# SD_USB_FMU_REV_2A.net
KiCad netlist of a schematic drawn in Altium Designer
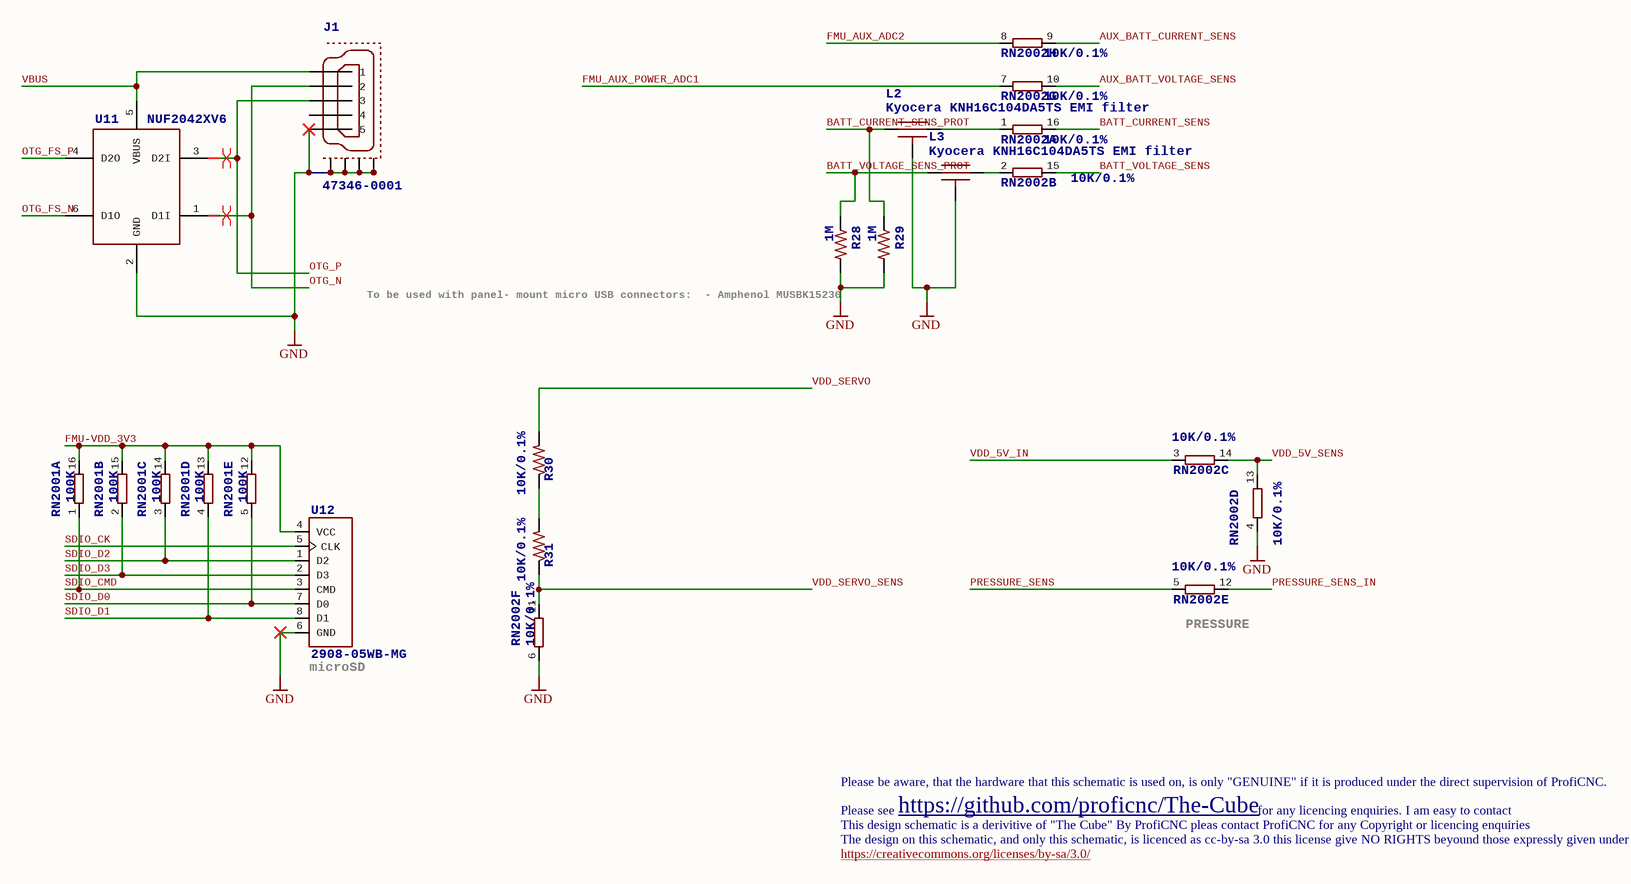
[diagram p0: SD_USB_FMU_REV_2A.SchDoc]

(export (version "E")
  (design (tool "Eeschema 10.0.6"))
  (components
    (comp (ref "J1")
      (value "47346-0001")
      (footprint "MOLEX-47346-0001")
      (description "MICRO USB B, BOTTOM MOUNT")
      (libsource (lib "pixhawk2") (part "MOLEX-47346-0001"))
    )
    (comp (ref "L2")
      (value "Kyocera KNH16C104DA5TS EMI filter")
      (footprint "KYOCERA-KNH16-DA")
      (description "FILTER CAP 0.1UF 2A 25V 0603")
      (libsource (lib "pixhawk2") (part "KNH16C104DA5TS"))
    )
    (comp (ref "L3")
      (value "Kyocera KNH16C104DA5TS EMI filter")
      (footprint "KYOCERA-KNH16-DA")
      (description "FILTER CAP 0.1UF 2A 25V 0603")
      (libsource (lib "pixhawk2") (part "KNH16C104DA5TS"))
    )
    (comp (ref "R28")
      (value "1M")
      (footprint "0402-RES")
      (description "RES 1M OHM 1/16W 1% 0402 SMD")
      (libsource (lib "pixhawk2") (part "RESISTOR0402-RES"))
    )
    (comp (ref "R29")
      (value "1M")
      (footprint "0402-RES")
      (description "RES 1M OHM 1/16W 1% 0402 SMD")
      (libsource (lib "pixhawk2") (part "RESISTOR0402-RES"))
    )
    (comp (ref "R30")
      (value "10K/0.1%")
      (footprint "0402-RES")
      (description "RES 10K OHM 1/16W .1% 0402 SMD")
      (libsource (lib "pixhawk2") (part "RESISTOR0402-RES"))
    )
    (comp (ref "R31")
      (value "10K/0.1%")
      (footprint "0402-RES")
      (description "RES 10K OHM 1/16W .1% 0402 SMD")
      (libsource (lib "pixhawk2") (part "RESISTOR0402-RES"))
    )
    (comp (ref "RN2001")
      (value "100K")
      (footprint "EXB2HV")
      (description "RES ARRAY 100K OHM 8 RES 1506")
      (libsource (lib "pixhawk2") (part "8R-NEXB2HV-100K"))
    )
    (comp (ref "RN2002")
      (value "10K/0.1%")
      (footprint "EXB2HV")
      (description "RES ARRAY 10K OHM 8 RES 1506")
      (libsource (lib "pixhawk2") (part "8R-NEXB2HV-10K"))
    )
    (comp (ref "U11")
      (value "NUF2042XV6")
      (footprint "SOT563-6")
      (description "IC FILTER USB ESD PROTECT SOT363")
      (libsource (lib "pixhawk2") (part "NUF2042XV6"))
    )
    (comp (ref "U12")
      (value "2908-05WB-MG")
      (footprint "MICROSD")
      (description "CONN MICRO SD CARD PUSH-PUSH R/A")
      (libsource (lib "baseboard") (part "MICROSDSDI"))
    )
  )
  (nets
    (net (code "1") (name "/AUX_BATT_CURRENT_SENS") (class "Default")
      (node (ref "RN2002") (pin "9") (pinfunction "2_9") (pintype "passive"))
    )
    (net (code "2") (name "/AUX_BATT_VOLTAGE_SENS") (class "Default")
      (node (ref "RN2002") (pin "10") (pinfunction "2_10") (pintype "passive"))
    )
    (net (code "3") (name "/BATT_CURRENT_SENS") (class "Default")
      (node (ref "RN2002") (pin "16") (pinfunction "2_16") (pintype "passive"))
    )
    (net (code "4") (name "/BATT_CURRENT_SENS_PROT") (class "Default")
      (node (ref "L2") (pin "P$1") (pinfunction "P$1_P$1") (pintype "passive"))
      (node (ref "R29") (pin "P$1") (pinfunction "1_P$1") (pintype "passive"))
    )
    (net (code "5") (name "/BATT_VOLTAGE_SENS") (class "Default")
      (node (ref "RN2002") (pin "15") (pinfunction "2_15") (pintype "passive"))
    )
    (net (code "6") (name "/BATT_VOLTAGE_SENS_PROT") (class "Default")
      (node (ref "L3") (pin "P$1") (pinfunction "P$1_P$1") (pintype "passive"))
      (node (ref "R28") (pin "P$1") (pinfunction "1_P$1") (pintype "passive"))
    )
    (net (code "7") (name "/FMU-VDD_3V3") (class "Default")
      (node (ref "RN2001") (pin "12") (pinfunction "2_12") (pintype "passive"))
      (node (ref "RN2001") (pin "13") (pinfunction "2_13") (pintype "passive"))
      (node (ref "RN2001") (pin "14") (pinfunction "2_14") (pintype "passive"))
      (node (ref "RN2001") (pin "15") (pinfunction "2_15") (pintype "passive"))
      (node (ref "RN2001") (pin "16") (pinfunction "2_16") (pintype "passive"))
      (node (ref "U12") (pin "4") (pinfunction "VCC_4") (pintype "passive"))
    )
    (net (code "8") (name "/FMU_AUX_ADC2") (class "Default")
      (node (ref "RN2002") (pin "8") (pinfunction "1_8") (pintype "passive"))
    )
    (net (code "9") (name "/FMU_AUX_POWER_ADC1") (class "Default")
      (node (ref "RN2002") (pin "7") (pinfunction "1_7") (pintype "passive"))
    )
    (net (code "10") (name "/OTG_FS_N") (class "Default")
      (node (ref "U11") (pin "6") (pinfunction "D1O_6") (pintype "passive"))
    )
    (net (code "11") (name "/OTG_FS_P") (class "Default")
      (node (ref "U11") (pin "4") (pinfunction "D2O_4") (pintype "passive"))
    )
    (net (code "12") (name "/OTG_N") (class "Default")
      (node (ref "J1") (pin "D-") (pinfunction "2_D-") (pintype "passive"))
      (node (ref "U11") (pin "1") (pinfunction "D1I_1") (pintype "passive"))
    )
    (net (code "13") (name "/OTG_P") (class "Default")
      (node (ref "J1") (pin "D+") (pinfunction "3_D+") (pintype "passive"))
      (node (ref "U11") (pin "3") (pinfunction "D2I_3") (pintype "passive"))
    )
    (net (code "14") (name "/PRESSURE_SENS") (class "Default")
      (node (ref "RN2002") (pin "5") (pinfunction "1_5") (pintype "passive"))
    )
    (net (code "15") (name "/PRESSURE_SENS_IN") (class "Default")
      (node (ref "RN2002") (pin "12") (pinfunction "2_12") (pintype "passive"))
    )
    (net (code "16") (name "/SDIO_CK") (class "Default")
      (node (ref "U12") (pin "5") (pinfunction "CLK_5") (pintype "passive"))
    )
    (net (code "17") (name "/SDIO_CMD") (class "Default")
      (node (ref "RN2001") (pin "1") (pinfunction "1_1") (pintype "passive"))
      (node (ref "U12") (pin "3") (pinfunction "CMD_3") (pintype "passive"))
    )
    (net (code "18") (name "/SDIO_D0") (class "Default")
      (node (ref "RN2001") (pin "5") (pinfunction "1_5") (pintype "passive"))
      (node (ref "U12") (pin "7") (pinfunction "D0_7") (pintype "passive"))
    )
    (net (code "19") (name "/SDIO_D1") (class "Default")
      (node (ref "RN2001") (pin "4") (pinfunction "1_4") (pintype "passive"))
      (node (ref "U12") (pin "8") (pinfunction "D1_8") (pintype "passive"))
    )
    (net (code "20") (name "/SDIO_D2") (class "Default")
      (node (ref "RN2001") (pin "3") (pinfunction "1_3") (pintype "passive"))
      (node (ref "U12") (pin "1") (pinfunction "D2_1") (pintype "passive"))
    )
    (net (code "21") (name "/SDIO_D3") (class "Default")
      (node (ref "RN2001") (pin "2") (pinfunction "1_2") (pintype "passive"))
      (node (ref "U12") (pin "2") (pinfunction "D3_2") (pintype "passive"))
    )
    (net (code "22") (name "/VBUS") (class "Default")
      (node (ref "J1") (pin "VBUS") (pinfunction "1_VBUS") (pintype "open_emitter"))
      (node (ref "U11") (pin "5") (pinfunction "VBUS_5") (pintype "passive"))
    )
    (net (code "23") (name "/VDD_5V_IN") (class "Default")
      (node (ref "RN2002") (pin "3") (pinfunction "1_3") (pintype "passive"))
    )
    (net (code "24") (name "/VDD_5V_SENS") (class "Default")
      (node (ref "RN2002") (pin "13") (pinfunction "2_13") (pintype "passive"))
      (node (ref "RN2002") (pin "14") (pinfunction "2_14") (pintype "passive"))
    )
    (net (code "25") (name "/VDD_SERVO") (class "Default")
      (node (ref "R30") (pin "P$2") (pinfunction "2_P$2") (pintype "passive"))
    )
    (net (code "26") (name "/VDD_SERVO_SENS") (class "Default")
      (node (ref "R31") (pin "P$1") (pinfunction "1_P$1") (pintype "passive"))
      (node (ref "RN2002") (pin "11") (pinfunction "2_11") (pintype "passive"))
    )
    (net (code "27") (name "GND") (class "Default")
      (node (ref "J1") (pin "GND") (pinfunction "5_GND") (pintype "open_emitter"))
      (node (ref "J1") (pin "GND1") (pinfunction "GND1_GND1") (pintype "passive"))
      (node (ref "J1") (pin "GND2") (pinfunction "GND2_GND2") (pintype "passive"))
      (node (ref "J1") (pin "GND3") (pinfunction "GND3_GND3") (pintype "passive"))
      (node (ref "J1") (pin "GND4") (pinfunction "GND4_GND4") (pintype "passive"))
      (node (ref "L2") (pin "GND") (pinfunction "GND_GND") (pintype "passive"))
      (node (ref "L3") (pin "GND") (pinfunction "GND_GND") (pintype "passive"))
      (node (ref "R28") (pin "P$2") (pinfunction "2_P$2") (pintype "passive"))
      (node (ref "R29") (pin "P$2") (pinfunction "2_P$2") (pintype "passive"))
      (node (ref "RN2002") (pin "4") (pinfunction "1_4") (pintype "passive"))
      (node (ref "RN2002") (pin "6") (pinfunction "1_6") (pintype "passive"))
      (node (ref "U11") (pin "2") (pinfunction "GND_2") (pintype "passive"))
      (node (ref "U12") (pin "6") (pinfunction "GND_6") (pintype "open_emitter"))
    )
    (net (code "28") (name "Net-(L2-PadP$2)") (class "Default")
      (node (ref "L2") (pin "P$2") (pinfunction "P$2_P$2") (pintype "passive"))
      (node (ref "RN2002") (pin "1") (pinfunction "1_1") (pintype "passive"))
    )
    (net (code "29") (name "Net-(R30-1)") (class "Default")
      (node (ref "R30") (pin "P$1") (pinfunction "1_P$1") (pintype "passive"))
      (node (ref "R31") (pin "P$2") (pinfunction "2_P$2") (pintype "passive"))
    )
    (net (code "30") (name "Net-(RN2002B-1)") (class "Default")
      (node (ref "L3") (pin "P$2") (pinfunction "P$2_P$2") (pintype "passive"))
      (node (ref "RN2002") (pin "2") (pinfunction "1_2") (pintype "passive"))
    )
    (net (code "31") (name "unconnected-(J1-4-PadID)") (class "Default")
      (node (ref "J1") (pin "ID") (pinfunction "4_ID") (pintype "passive"))
    )
  )
)
